# untitled.net
KiCad netlist of a schematic drawn in EAGLE
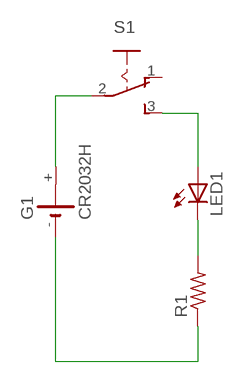
[diagram p0: schematic, sheet 1]

(export (version "E")
  (design (tool "Eeschema 10.0.6"))
  (components
    (comp (ref "G1")
      (value "CR2032H")
      (footprint "eagle-import:CR2032H")
      (libsource (lib "eagle-import") (part "CR2032H"))
    )
    (comp (ref "LED1")
      (value "LED5MM")
      (footprint "eagle-import:LED5MM")
      (libsource (lib "eagle-import") (part "LED5MM"))
    )
    (comp (ref "R1")
      (value "R-US_0207/10")
      (footprint "eagle-import:0207_10")
      (libsource (lib "eagle-import") (part "R-US_0207/10"))
    )
    (comp (ref "S1")
      (value "255SB")
      (footprint "eagle-import:255SB")
      (libsource (lib "eagle-import") (part "255SB"))
    )
  )
  (nets
    (net (code "1") (name "Net-(G1-Pad-)") (class "Default")
      (node (ref "G1") (pin "-") (pinfunction "-_-") (pintype "passive"))
      (node (ref "R1") (pin "1") (pinfunction "1_1") (pintype "passive"))
    )
    (net (code "2") (name "Net-(LED1-C)") (class "Default")
      (node (ref "LED1") (pin "K") (pinfunction "C_K") (pintype "passive"))
      (node (ref "R1") (pin "2") (pinfunction "2_2") (pintype "passive"))
    )
    (net (code "3") (name "Net-(S1-P)") (class "Default")
      (node (ref "G1") (pin "+") (pinfunction "+_+") (pintype "passive"))
      (node (ref "S1") (pin "2") (pinfunction "P_2") (pintype "passive"))
    )
    (net (code "4") (name "Net-(S1-S)") (class "Default")
      (node (ref "LED1") (pin "A") (pinfunction "A_A") (pintype "passive"))
      (node (ref "S1") (pin "3") (pinfunction "S_3") (pintype "passive"))
    )
    (net (code "5") (name "unconnected-(G1-+-Pad+@1)") (class "Default")
      (node (ref "G1") (pin "+@1") (pinfunction "+_+@1") (pintype "passive"))
    )
    (net (code "6") (name "unconnected-(S1-O-Pad1)") (class "Default")
      (node (ref "S1") (pin "1") (pinfunction "O_1") (pintype "passive"))
    )
  )
)
